# ct_fpga_io.net
KiCad netlist of a schematic drawn in Altium Designer
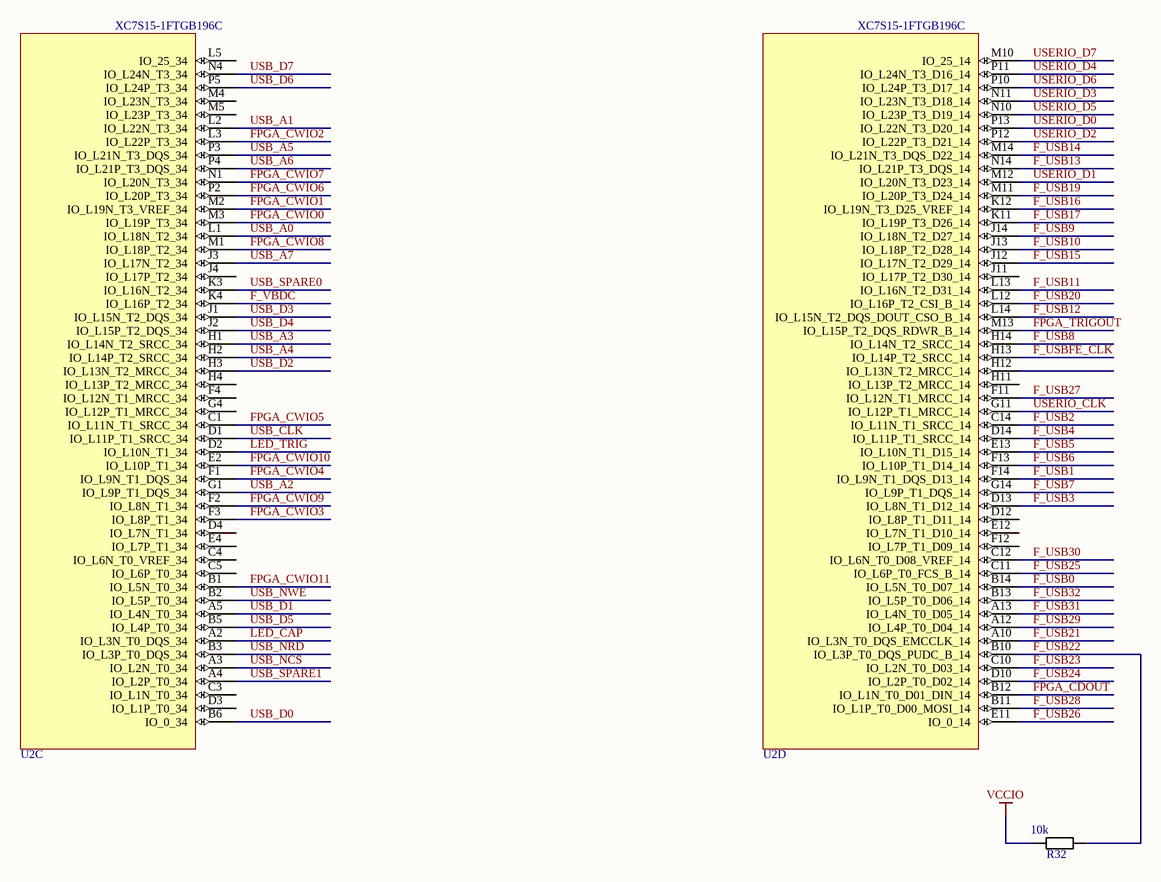
[diagram p0: ct_fpga_io.SchDoc]

(export (version "E")
  (design (tool "Eeschema 10.0.6"))
  (components
    (comp (ref "R32")
      (value "10k")
      (footprint "RESC1608X55N")
      (description "10k res, 0603, 1%, 1/10W")
      (fields (field (name "PART NUMBER") "RCHIP-10K-0603") (field (name "TOLERANCE") "1%"))
      (libsource (lib "NewAE_AltiumLib") (part "RES-EU"))
    )
    (comp (ref "U2")
      (value "XC7S15-1FTGB196C")
      (footprint "BGA_FTGB196")
      (description "Xilinx Spartan 7 FPGA, 196FTGB")
      (libsource (lib "NewAE_AltiumLib") (part "XC7S6FTGB196"))
    )
  )
  (nets
    (net (code "1") (name "/FPGA_CDOUT") (class "Default")
      (node (ref "U2") (pin "B12") (pinfunction "IO_L1N_T0_D01_DIN_14_B12") (pintype "bidirectional"))
    )
    (net (code "2") (name "/FPGA_CWIO0") (class "Default")
      (node (ref "U2") (pin "M3") (pinfunction "IO_L19P_T3_34_M3") (pintype "bidirectional"))
    )
    (net (code "3") (name "/FPGA_CWIO1") (class "Default")
      (node (ref "U2") (pin "M2") (pinfunction "IO_L19N_T3_VREF_34_M2") (pintype "bidirectional"))
    )
    (net (code "4") (name "/FPGA_CWIO2") (class "Default")
      (node (ref "U2") (pin "L3") (pinfunction "IO_L22P_T3_34_L3") (pintype "bidirectional"))
    )
    (net (code "5") (name "/FPGA_CWIO3") (class "Default")
      (node (ref "U2") (pin "F3") (pinfunction "IO_L8P_T1_34_F3") (pintype "bidirectional"))
    )
    (net (code "6") (name "/FPGA_CWIO4") (class "Default")
      (node (ref "U2") (pin "F1") (pinfunction "IO_L9N_T1_DQS_34_F1") (pintype "bidirectional"))
    )
    (net (code "7") (name "/FPGA_CWIO5") (class "Default")
      (node (ref "U2") (pin "C1") (pinfunction "IO_L11N_T1_SRCC_34_C1") (pintype "bidirectional"))
    )
    (net (code "8") (name "/FPGA_CWIO6") (class "Default")
      (node (ref "U2") (pin "P2") (pinfunction "IO_L20P_T3_34_P2") (pintype "bidirectional"))
    )
    (net (code "9") (name "/FPGA_CWIO7") (class "Default")
      (node (ref "U2") (pin "N1") (pinfunction "IO_L20N_T3_34_N1") (pintype "bidirectional"))
    )
    (net (code "10") (name "/FPGA_CWIO8") (class "Default")
      (node (ref "U2") (pin "M1") (pinfunction "IO_L18P_T2_34_M1") (pintype "bidirectional"))
    )
    (net (code "11") (name "/FPGA_CWIO9") (class "Default")
      (node (ref "U2") (pin "F2") (pinfunction "IO_L8N_T1_34_F2") (pintype "bidirectional"))
    )
    (net (code "12") (name "/FPGA_CWIO10") (class "Default")
      (node (ref "U2") (pin "E2") (pinfunction "IO_L10P_T1_34_E2") (pintype "bidirectional"))
    )
    (net (code "13") (name "/FPGA_CWIO11") (class "Default")
      (node (ref "U2") (pin "B1") (pinfunction "IO_L5N_T0_34_B1") (pintype "bidirectional"))
    )
    (net (code "14") (name "/FPGA_TRIGOUT") (class "Default")
      (node (ref "U2") (pin "M13") (pinfunction "IO_L15P_T2_DQS_RDWR_B_14_M13") (pintype "bidirectional"))
    )
    (net (code "15") (name "/F_USB0") (class "Default")
      (node (ref "U2") (pin "B14") (pinfunction "IO_L5N_T0_D07_14_B14") (pintype "bidirectional"))
    )
    (net (code "16") (name "/F_USB1") (class "Default")
      (node (ref "U2") (pin "F14") (pinfunction "IO_L9N_T1_DQS_D13_14_F14") (pintype "bidirectional"))
    )
    (net (code "17") (name "/F_USB2") (class "Default")
      (node (ref "U2") (pin "C14") (pinfunction "IO_L11N_T1_SRCC_14_C14") (pintype "bidirectional"))
    )
    (net (code "18") (name "/F_USB3") (class "Default")
      (node (ref "U2") (pin "D13") (pinfunction "IO_L8N_T1_D12_14_D13") (pintype "bidirectional"))
    )
    (net (code "19") (name "/F_USB4") (class "Default")
      (node (ref "U2") (pin "D14") (pinfunction "IO_L11P_T1_SRCC_14_D14") (pintype "bidirectional"))
    )
    (net (code "20") (name "/F_USB5") (class "Default")
      (node (ref "U2") (pin "E13") (pinfunction "IO_L10N_T1_D15_14_E13") (pintype "bidirectional"))
    )
    (net (code "21") (name "/F_USB6") (class "Default")
      (node (ref "U2") (pin "F13") (pinfunction "IO_L10P_T1_D14_14_F13") (pintype "bidirectional"))
    )
    (net (code "22") (name "/F_USB7") (class "Default")
      (node (ref "U2") (pin "G14") (pinfunction "IO_L9P_T1_DQS_14_G14") (pintype "bidirectional"))
    )
    (net (code "23") (name "/F_USB8") (class "Default")
      (node (ref "U2") (pin "H14") (pinfunction "IO_L14N_T2_SRCC_14_H14") (pintype "bidirectional"))
    )
    (net (code "24") (name "/F_USB9") (class "Default")
      (node (ref "U2") (pin "J14") (pinfunction "IO_L18N_T2_D27_14_J14") (pintype "bidirectional"))
    )
    (net (code "25") (name "/F_USB10") (class "Default")
      (node (ref "U2") (pin "J13") (pinfunction "IO_L18P_T2_D28_14_J13") (pintype "bidirectional"))
    )
    (net (code "26") (name "/F_USB11") (class "Default")
      (node (ref "U2") (pin "L13") (pinfunction "IO_L16N_T2_D31_14_L13") (pintype "bidirectional"))
    )
    (net (code "27") (name "/F_USB12") (class "Default")
      (node (ref "U2") (pin "L14") (pinfunction "IO_L15N_T2_DQS_DOUT_CSO_B_14_L14") (pintype "bidirectional"))
    )
    (net (code "28") (name "/F_USB13") (class "Default")
      (node (ref "U2") (pin "N14") (pinfunction "IO_L21P_T3_DQS_14_N14") (pintype "bidirectional"))
    )
    (net (code "29") (name "/F_USB14") (class "Default")
      (node (ref "U2") (pin "M14") (pinfunction "IO_L21N_T3_DQS_D22_14_M14") (pintype "bidirectional"))
    )
    (net (code "30") (name "/F_USB15") (class "Default")
      (node (ref "U2") (pin "J12") (pinfunction "IO_L17N_T2_D29_14_J12") (pintype "bidirectional"))
    )
    (net (code "31") (name "/F_USB16") (class "Default")
      (node (ref "U2") (pin "K12") (pinfunction "IO_L19N_T3_D25_VREF_14_K12") (pintype "bidirectional"))
    )
    (net (code "32") (name "/F_USB17") (class "Default")
      (node (ref "U2") (pin "K11") (pinfunction "IO_L19P_T3_D26_14_K11") (pintype "bidirectional"))
    )
    (net (code "33") (name "/F_USB19") (class "Default")
      (node (ref "U2") (pin "M11") (pinfunction "IO_L20P_T3_D24_14_M11") (pintype "bidirectional"))
    )
    (net (code "34") (name "/F_USB20") (class "Default")
      (node (ref "U2") (pin "L12") (pinfunction "IO_L16P_T2_CSI_B_14_L12") (pintype "bidirectional"))
    )
    (net (code "35") (name "/F_USB21") (class "Default")
      (node (ref "U2") (pin "A10") (pinfunction "IO_L3N_T0_DQS_EMCCLK_14_A10") (pintype "bidirectional"))
    )
    (net (code "36") (name "/F_USB22") (class "Default")
      (node (ref "R32") (pin "2") (pinfunction "2_2") (pintype "passive"))
      (node (ref "U2") (pin "B10") (pinfunction "IO_L3P_T0_DQS_PUDC_B_14_B10") (pintype "bidirectional"))
    )
    (net (code "37") (name "/F_USB23") (class "Default")
      (node (ref "U2") (pin "C10") (pinfunction "IO_L2N_T0_D03_14_C10") (pintype "bidirectional"))
    )
    (net (code "38") (name "/F_USB24") (class "Default")
      (node (ref "U2") (pin "D10") (pinfunction "IO_L2P_T0_D02_14_D10") (pintype "bidirectional"))
    )
    (net (code "39") (name "/F_USB25") (class "Default")
      (node (ref "U2") (pin "C11") (pinfunction "IO_L6P_T0_FCS_B_14_C11") (pintype "bidirectional"))
    )
    (net (code "40") (name "/F_USB26") (class "Default")
      (node (ref "U2") (pin "E11") (pinfunction "IO_0_14_E11") (pintype "bidirectional"))
    )
    (net (code "41") (name "/F_USB27") (class "Default")
      (node (ref "U2") (pin "F11") (pinfunction "IO_L12N_T1_MRCC_14_F11") (pintype "bidirectional"))
    )
    (net (code "42") (name "/F_USB28") (class "Default")
      (node (ref "U2") (pin "B11") (pinfunction "IO_L1P_T0_D00_MOSI_14_B11") (pintype "bidirectional"))
    )
    (net (code "43") (name "/F_USB29") (class "Default")
      (node (ref "U2") (pin "A12") (pinfunction "IO_L4P_T0_D04_14_A12") (pintype "bidirectional"))
    )
    (net (code "44") (name "/F_USB30") (class "Default")
      (node (ref "U2") (pin "C12") (pinfunction "IO_L6N_T0_D08_VREF_14_C12") (pintype "bidirectional"))
    )
    (net (code "45") (name "/F_USB31") (class "Default")
      (node (ref "U2") (pin "A13") (pinfunction "IO_L4N_T0_D05_14_A13") (pintype "bidirectional"))
    )
    (net (code "46") (name "/F_USB32") (class "Default")
      (node (ref "U2") (pin "B13") (pinfunction "IO_L5P_T0_D06_14_B13") (pintype "bidirectional"))
    )
    (net (code "47") (name "/F_USBFE_CLK") (class "Default")
      (node (ref "U2") (pin "H13") (pinfunction "IO_L14P_T2_SRCC_14_H13") (pintype "bidirectional"))
    )
    (net (code "48") (name "/F_VBDC") (class "Default")
      (node (ref "U2") (pin "K4") (pinfunction "IO_L16P_T2_34_K4") (pintype "bidirectional"))
    )
    (net (code "49") (name "/LED_CAP") (class "Default")
      (node (ref "U2") (pin "A2") (pinfunction "IO_L3N_T0_DQS_34_A2") (pintype "bidirectional"))
    )
    (net (code "50") (name "/LED_TRIG") (class "Default")
      (node (ref "U2") (pin "D2") (pinfunction "IO_L10N_T1_34_D2") (pintype "bidirectional"))
    )
    (net (code "51") (name "/USB_A0") (class "Default")
      (node (ref "U2") (pin "L1") (pinfunction "IO_L18N_T2_34_L1") (pintype "bidirectional"))
    )
    (net (code "52") (name "/USB_A1") (class "Default")
      (node (ref "U2") (pin "L2") (pinfunction "IO_L22N_T3_34_L2") (pintype "bidirectional"))
    )
    (net (code "53") (name "/USB_A2") (class "Default")
      (node (ref "U2") (pin "G1") (pinfunction "IO_L9P_T1_DQS_34_G1") (pintype "bidirectional"))
    )
    (net (code "54") (name "/USB_A3") (class "Default")
      (node (ref "U2") (pin "H1") (pinfunction "IO_L14N_T2_SRCC_34_H1") (pintype "bidirectional"))
    )
    (net (code "55") (name "/USB_A4") (class "Default")
      (node (ref "U2") (pin "H2") (pinfunction "IO_L14P_T2_SRCC_34_H2") (pintype "bidirectional"))
    )
    (net (code "56") (name "/USB_A5") (class "Default")
      (node (ref "U2") (pin "P3") (pinfunction "IO_L21N_T3_DQS_34_P3") (pintype "bidirectional"))
    )
    (net (code "57") (name "/USB_A6") (class "Default")
      (node (ref "U2") (pin "P4") (pinfunction "IO_L21P_T3_DQS_34_P4") (pintype "bidirectional"))
    )
    (net (code "58") (name "/USB_A7") (class "Default")
      (node (ref "U2") (pin "J3") (pinfunction "IO_L17N_T2_34_J3") (pintype "bidirectional"))
    )
    (net (code "59") (name "/USB_CLK") (class "Default")
      (node (ref "U2") (pin "D1") (pinfunction "IO_L11P_T1_SRCC_34_D1") (pintype "bidirectional"))
    )
    (net (code "60") (name "/USB_D0") (class "Default")
      (node (ref "U2") (pin "B6") (pinfunction "IO_0_34_B6") (pintype "bidirectional"))
    )
    (net (code "61") (name "/USB_D1") (class "Default")
      (node (ref "U2") (pin "A5") (pinfunction "IO_L4N_T0_34_A5") (pintype "bidirectional"))
    )
    (net (code "62") (name "/USB_D2") (class "Default")
      (node (ref "U2") (pin "H3") (pinfunction "IO_L13N_T2_MRCC_34_H3") (pintype "bidirectional"))
    )
    (net (code "63") (name "/USB_D3") (class "Default")
      (node (ref "U2") (pin "J1") (pinfunction "IO_L15N_T2_DQS_34_J1") (pintype "bidirectional"))
    )
    (net (code "64") (name "/USB_D4") (class "Default")
      (node (ref "U2") (pin "J2") (pinfunction "IO_L15P_T2_DQS_34_J2") (pintype "bidirectional"))
    )
    (net (code "65") (name "/USB_D5") (class "Default")
      (node (ref "U2") (pin "B5") (pinfunction "IO_L4P_T0_34_B5") (pintype "bidirectional"))
    )
    (net (code "66") (name "/USB_D6") (class "Default")
      (node (ref "U2") (pin "P5") (pinfunction "IO_L24P_T3_34_P5") (pintype "bidirectional"))
    )
    (net (code "67") (name "/USB_D7") (class "Default")
      (node (ref "U2") (pin "N4") (pinfunction "IO_L24N_T3_34_N4") (pintype "bidirectional"))
    )
    (net (code "68") (name "/USB_NCS") (class "Default")
      (node (ref "U2") (pin "A3") (pinfunction "IO_L2N_T0_34_A3") (pintype "bidirectional"))
    )
    (net (code "69") (name "/USB_NRD") (class "Default")
      (node (ref "U2") (pin "B3") (pinfunction "IO_L3P_T0_DQS_34_B3") (pintype "bidirectional"))
    )
    (net (code "70") (name "/USB_NWE") (class "Default")
      (node (ref "U2") (pin "B2") (pinfunction "IO_L5P_T0_34_B2") (pintype "bidirectional"))
    )
    (net (code "71") (name "/USB_SPARE0") (class "Default")
      (node (ref "U2") (pin "K3") (pinfunction "IO_L16N_T2_34_K3") (pintype "bidirectional"))
    )
    (net (code "72") (name "/USB_SPARE1") (class "Default")
      (node (ref "U2") (pin "A4") (pinfunction "IO_L2P_T0_34_A4") (pintype "bidirectional"))
    )
    (net (code "73") (name "/USERIO_CLK") (class "Default")
      (node (ref "U2") (pin "G11") (pinfunction "IO_L12P_T1_MRCC_14_G11") (pintype "bidirectional"))
    )
    (net (code "74") (name "/USERIO_D0") (class "Default")
      (node (ref "U2") (pin "P13") (pinfunction "IO_L22N_T3_D20_14_P13") (pintype "bidirectional"))
    )
    (net (code "75") (name "/USERIO_D1") (class "Default")
      (node (ref "U2") (pin "M12") (pinfunction "IO_L20N_T3_D23_14_M12") (pintype "bidirectional"))
    )
    (net (code "76") (name "/USERIO_D2") (class "Default")
      (node (ref "U2") (pin "P12") (pinfunction "IO_L22P_T3_D21_14_P12") (pintype "bidirectional"))
    )
    (net (code "77") (name "/USERIO_D3") (class "Default")
      (node (ref "U2") (pin "N11") (pinfunction "IO_L23N_T3_D18_14_N11") (pintype "bidirectional"))
    )
    (net (code "78") (name "/USERIO_D4") (class "Default")
      (node (ref "U2") (pin "P11") (pinfunction "IO_L24N_T3_D16_14_P11") (pintype "bidirectional"))
    )
    (net (code "79") (name "/USERIO_D5") (class "Default")
      (node (ref "U2") (pin "N10") (pinfunction "IO_L23P_T3_D19_14_N10") (pintype "bidirectional"))
    )
    (net (code "80") (name "/USERIO_D6") (class "Default")
      (node (ref "U2") (pin "P10") (pinfunction "IO_L24P_T3_D17_14_P10") (pintype "bidirectional"))
    )
    (net (code "81") (name "/USERIO_D7") (class "Default")
      (node (ref "U2") (pin "M10") (pinfunction "IO_25_14_M10") (pintype "bidirectional"))
    )
    (net (code "82") (name "VCCIO") (class "Default")
      (node (ref "R32") (pin "1") (pinfunction "1_1") (pintype "passive"))
    )
    (net (code "83") (name "unconnected-(U2C-IO_25_34-PadL5)") (class "Default")
      (node (ref "U2") (pin "L5") (pinfunction "IO_25_34_L5") (pintype "bidirectional"))
    )
    (net (code "84") (name "unconnected-(U2C-IO_L1N_T0_34-PadC3)") (class "Default")
      (node (ref "U2") (pin "C3") (pinfunction "IO_L1N_T0_34_C3") (pintype "bidirectional"))
    )
    (net (code "85") (name "unconnected-(U2C-IO_L1P_T0_34-PadD3)") (class "Default")
      (node (ref "U2") (pin "D3") (pinfunction "IO_L1P_T0_34_D3") (pintype "bidirectional"))
    )
    (net (code "86") (name "unconnected-(U2C-IO_L6N_T0_VREF_34-PadC4)") (class "Default")
      (node (ref "U2") (pin "C4") (pinfunction "IO_L6N_T0_VREF_34_C4") (pintype "bidirectional"))
    )
    (net (code "87") (name "unconnected-(U2C-IO_L6P_T0_34-PadC5)") (class "Default")
      (node (ref "U2") (pin "C5") (pinfunction "IO_L6P_T0_34_C5") (pintype "bidirectional"))
    )
    (net (code "88") (name "unconnected-(U2C-IO_L7N_T1_34-PadD4)") (class "Default")
      (node (ref "U2") (pin "D4") (pinfunction "IO_L7N_T1_34_D4") (pintype "bidirectional"))
    )
    (net (code "89") (name "unconnected-(U2C-IO_L7P_T1_34-PadE4)") (class "Default")
      (node (ref "U2") (pin "E4") (pinfunction "IO_L7P_T1_34_E4") (pintype "bidirectional"))
    )
    (net (code "90") (name "unconnected-(U2C-IO_L12N_T1_MRCC_34-PadF4)") (class "Default")
      (node (ref "U2") (pin "F4") (pinfunction "IO_L12N_T1_MRCC_34_F4") (pintype "bidirectional"))
    )
    (net (code "91") (name "unconnected-(U2C-IO_L12P_T1_MRCC_34-PadG4)") (class "Default")
      (node (ref "U2") (pin "G4") (pinfunction "IO_L12P_T1_MRCC_34_G4") (pintype "bidirectional"))
    )
    (net (code "92") (name "unconnected-(U2C-IO_L13P_T2_MRCC_34-PadH4)") (class "Default")
      (node (ref "U2") (pin "H4") (pinfunction "IO_L13P_T2_MRCC_34_H4") (pintype "bidirectional"))
    )
    (net (code "93") (name "unconnected-(U2C-IO_L17P_T2_34-PadJ4)") (class "Default")
      (node (ref "U2") (pin "J4") (pinfunction "IO_L17P_T2_34_J4") (pintype "bidirectional"))
    )
    (net (code "94") (name "unconnected-(U2C-IO_L23N_T3_34-PadM4)") (class "Default")
      (node (ref "U2") (pin "M4") (pinfunction "IO_L23N_T3_34_M4") (pintype "bidirectional"))
    )
    (net (code "95") (name "unconnected-(U2C-IO_L23P_T3_34-PadM5)") (class "Default")
      (node (ref "U2") (pin "M5") (pinfunction "IO_L23P_T3_34_M5") (pintype "bidirectional"))
    )
    (net (code "96") (name "unconnected-(U2D-IO_L7N_T1_D10_14-PadE12)") (class "Default")
      (node (ref "U2") (pin "E12") (pinfunction "IO_L7N_T1_D10_14_E12") (pintype "bidirectional"))
    )
    (net (code "97") (name "unconnected-(U2D-IO_L7P_T1_D09_14-PadF12)") (class "Default")
      (node (ref "U2") (pin "F12") (pinfunction "IO_L7P_T1_D09_14_F12") (pintype "bidirectional"))
    )
    (net (code "98") (name "unconnected-(U2D-IO_L8P_T1_D11_14-PadD12)") (class "Default")
      (node (ref "U2") (pin "D12") (pinfunction "IO_L8P_T1_D11_14_D12") (pintype "bidirectional"))
    )
    (net (code "99") (name "unconnected-(U2D-IO_L13N_T2_MRCC_14-PadH12)") (class "Default")
      (node (ref "U2") (pin "H12") (pinfunction "IO_L13N_T2_MRCC_14_H12") (pintype "bidirectional"))
    )
    (net (code "100") (name "unconnected-(U2D-IO_L13P_T2_MRCC_14-PadH11)") (class "Default")
      (node (ref "U2") (pin "H11") (pinfunction "IO_L13P_T2_MRCC_14_H11") (pintype "bidirectional"))
    )
    (net (code "101") (name "unconnected-(U2D-IO_L17P_T2_D30_14-PadJ11)") (class "Default")
      (node (ref "U2") (pin "J11") (pinfunction "IO_L17P_T2_D30_14_J11") (pintype "bidirectional"))
    )
  )
)
